# LD1086_30V_to_1V8.net
KiCad netlist of a schematic drawn in EAGLE
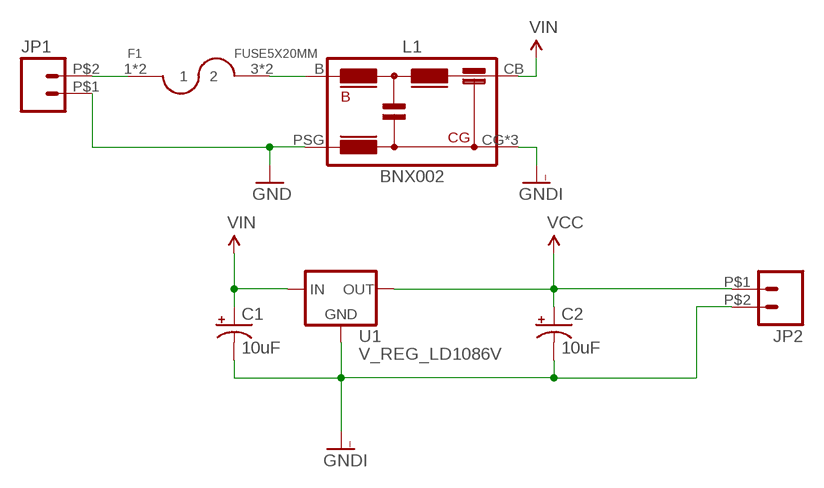
[diagram p0: schematic, sheet 1]

(export (version "E")
  (design (tool "Eeschema 10.0.6"))
  (components
    (comp (ref "C1")
      (value "10uF")
      (footprint "eagle-import:KEMET_E")
      (libsource (lib "eagle-import") (part "10UF-50V-10%(PTH)"))
    )
    (comp (ref "C2")
      (value "10uF")
      (footprint "eagle-import:KEMET_E")
      (libsource (lib "eagle-import") (part "10UF-50V-10%(PTH)"))
    )
    (comp (ref "F1")
      (value "FUSE5X20MM")
      (footprint "eagle-import:FUSE_1A3399")
      (libsource (lib "eagle-import") (part "FUSE5X20MM"))
    )
    (comp (ref "JP1")
      (value "M02TE-282834-2")
      (footprint "eagle-import:1X02_282834-2")
      (libsource (lib "eagle-import") (part "M02TE-282834-2"))
    )
    (comp (ref "JP2")
      (value "M02TE-282834-2")
      (footprint "eagle-import:1X02_282834-2")
      (libsource (lib "eagle-import") (part "M02TE-282834-2"))
    )
    (comp (ref "L1")
      (value "BNX002")
      (footprint "eagle-import:BNX002")
      (libsource (lib "eagle-import") (part "BNX002"))
    )
    (comp (ref "U1")
      (value "V_REG_LD1086V")
      (footprint "eagle-import:TO-220-SINGLE")
      (libsource (lib "eagle-import") (part "V_REG_LD1086V"))
    )
  )
  (nets
    (net (code "1") (name "GND") (class "Default")
      (node (ref "JP1") (pin "P$1") (pinfunction "1_P$1") (pintype "passive"))
      (node (ref "L1") (pin "PSG") (pinfunction "PSG_PSG") (pintype "passive"))
    )
    (net (code "2") (name "GNDI") (class "Default")
      (node (ref "C1") (pin "-") (pinfunction "-_-") (pintype "passive"))
      (node (ref "C2") (pin "-") (pinfunction "-_-") (pintype "passive"))
      (node (ref "JP2") (pin "P$2") (pinfunction "2_P$2") (pintype "passive"))
      (node (ref "L1") (pin "CG") (pinfunction "CG_CG") (pintype "passive"))
      (node (ref "L1") (pin "CG1") (pinfunction "CG_CG1") (pintype "passive"))
      (node (ref "L1") (pin "CG2") (pinfunction "CG_CG2") (pintype "passive"))
      (node (ref "U1") (pin "GND") (pinfunction "GND_GND") (pintype "passive"))
    )
    (net (code "3") (name "Net-(F1-2-Pad3)") (class "Default")
      (node (ref "F1") (pin "3") (pinfunction "2_3") (pintype "bidirectional"))
      (node (ref "F1") (pin "4") (pinfunction "2_4") (pintype "bidirectional"))
      (node (ref "L1") (pin "B") (pinfunction "B_B") (pintype "passive"))
    )
    (net (code "4") (name "Net-(JP1-2)") (class "Default")
      (node (ref "F1") (pin "1") (pinfunction "1_1") (pintype "bidirectional"))
      (node (ref "F1") (pin "2") (pinfunction "1_2") (pintype "bidirectional"))
      (node (ref "JP1") (pin "P$2") (pinfunction "2_P$2") (pintype "passive"))
    )
    (net (code "5") (name "VCC") (class "Default")
      (node (ref "C2") (pin "+") (pinfunction "+_+") (pintype "passive"))
      (node (ref "JP2") (pin "P$1") (pinfunction "1_P$1") (pintype "passive"))
      (node (ref "U1") (pin "OUT") (pinfunction "OUT_OUT") (pintype "output"))
    )
    (net (code "6") (name "VIN") (class "Default")
      (node (ref "C1") (pin "+") (pinfunction "+_+") (pintype "passive"))
      (node (ref "L1") (pin "CB") (pinfunction "CB_CB") (pintype "passive"))
      (node (ref "U1") (pin "IN") (pinfunction "IN_IN") (pintype "input"))
    )
  )
)
